# 14-MT7688AN_USB-PCIe.net
KiCad netlist of a schematic drawn in Altium Designer
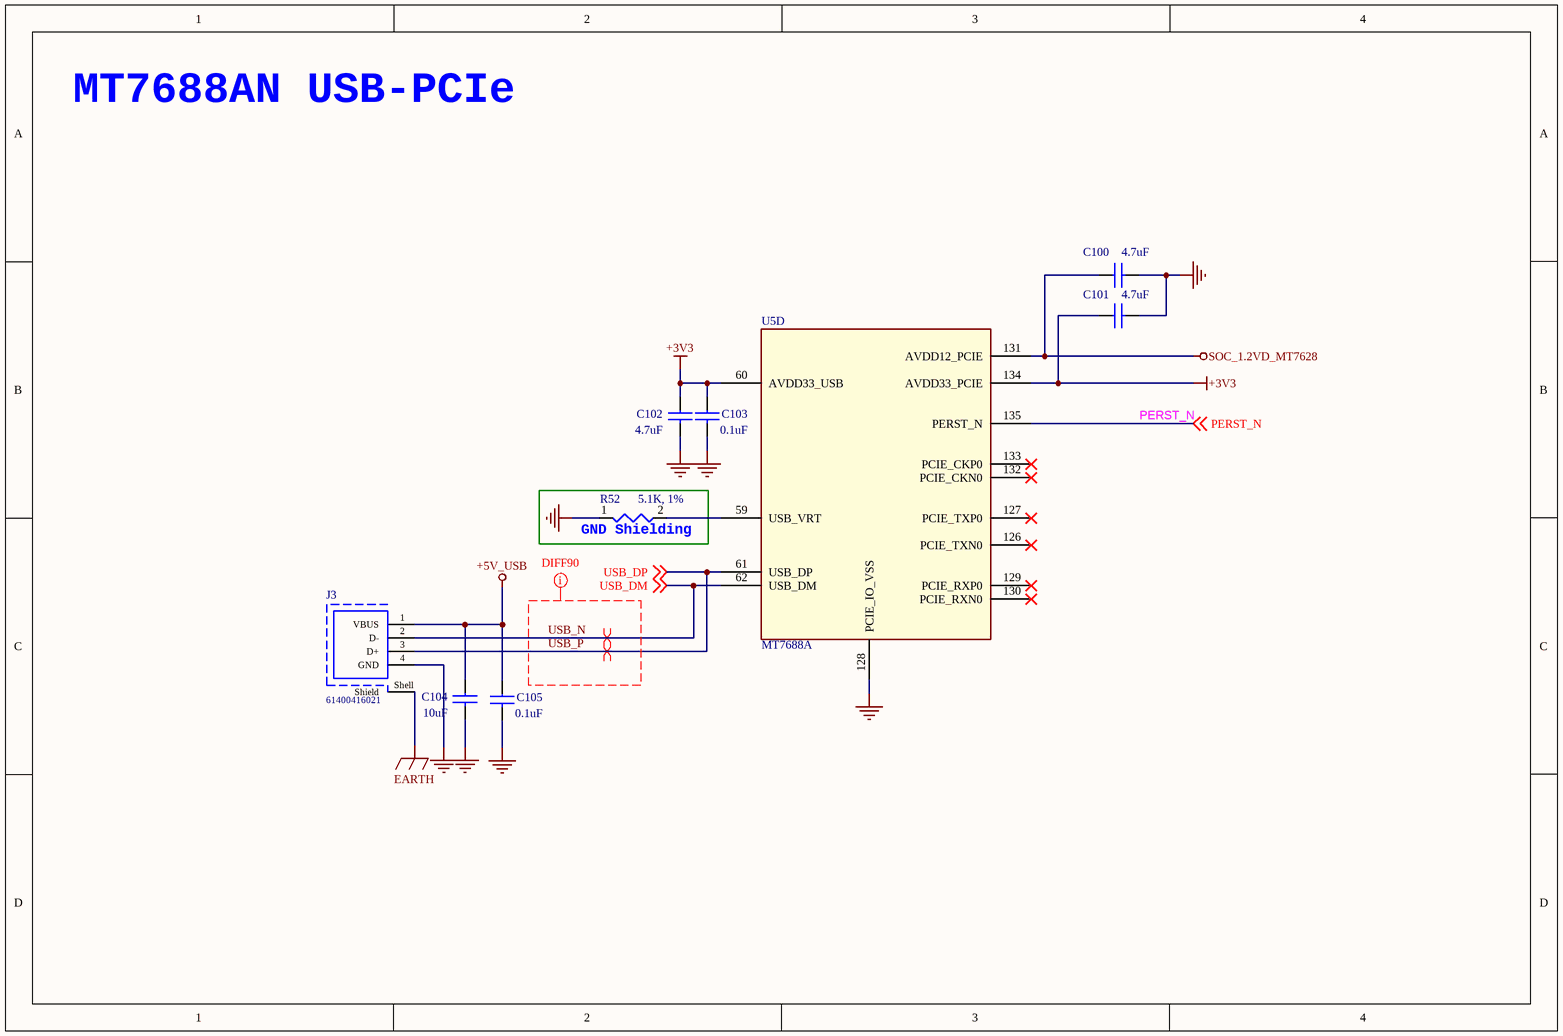
[diagram p0: 14-MT7688AN USB-PCIe.SchDoc]

(export (version "E")
  (design (tool "Eeschema 10.0.6"))
  (components
    (comp (ref "C100")
      (value "4.7uF")
      (footprint "CAPC1005X60X30LL05T10 - duplicate")
      (libsource (lib "MT7688AN") (part "CAP NP"))
    )
    (comp (ref "C101")
      (value "4.7uF")
      (footprint "CAPC1005X60X30LL05T10 - duplicate")
      (libsource (lib "MT7688AN") (part "CAP NP"))
    )
    (comp (ref "C102")
      (value "4.7uF")
      (footprint "CAPC1005X60X30NL05T10")
      (libsource (lib "MT7688AN") (part "CAP NP"))
    )
    (comp (ref "C103")
      (value "0.1uF")
      (footprint "CAPC1005X60X30NL05T10")
      (libsource (lib "MT7688AN") (part "CAP NP"))
    )
    (comp (ref "C104")
      (value "10uF")
      (footprint "CAPC1608X90X35NL10T15")
      (libsource (lib "MT7688AN") (part "CAP NP"))
    )
    (comp (ref "C105")
      (value "0.1uF")
      (footprint "CAPC1005X60X30LL05T10 - duplicate")
      (libsource (lib "MT7688AN") (part "CAP NP"))
    )
    (comp (ref "J3")
      (value "61400416021")
      (footprint "61400416021")
      (description "USB 2.0 Type A Receptacle WR-COM, Horizontal, THT")
      (fields (field (name "MANUFACTURER") "Wurth Elektronik") (field (name "PUBLISHER") "WurthElektronik"))
      (libsource (lib "Altium Content Vault") (part "WE-USB-4-1SHLD"))
    )
    (comp (ref "R52")
      (value "5.1K, 1%")
      (footprint "RESC1005X40X25NL05T10 - duplicate")
      (libsource (lib "MT7688AN") (part "RES/0402_3"))
    )
    (comp (ref "U5")
      (value "MT7688A")
      (footprint "MT7628AN$2F$DRQFN156$2F$SMD$2F$P0.5$2F$12X12")
      (libsource (lib "MT7688AN") (part "MT7620N-n_26"))
    )
  )
  (nets
    (net (code "1") (name "+3V3") (class "Default")
      (node (ref "C101") (pin "1") (pinfunction "1_1") (pintype "passive"))
      (node (ref "C102") (pin "1") (pinfunction "1_1") (pintype "passive"))
      (node (ref "C103") (pin "1") (pinfunction "1_1") (pintype "passive"))
      (node (ref "U5") (pin "134") (pinfunction "AVDD33_PCIE_134") (pintype "power_in"))
      (node (ref "U5") (pin "60") (pinfunction "AVDD33_USB_60") (pintype "passive"))
    )
    (net (code "2") (name "+5V_USB") (class "Default")
      (node (ref "C104") (pin "1") (pinfunction "1_1") (pintype "passive"))
      (node (ref "C105") (pin "1") (pinfunction "1_1") (pintype "passive"))
      (node (ref "J3") (pin "1") (pinfunction "VBUS_1") (pintype "passive"))
    )
    (net (code "3") (name "EARTH") (class "Default")
      (node (ref "J3") (pin "Shell") (pinfunction "Shield_Shell") (pintype "passive"))
    )
    (net (code "4") (name "GND") (class "Default")
      (node (ref "C100") (pin "2") (pinfunction "2_2") (pintype "passive"))
      (node (ref "C101") (pin "2") (pinfunction "2_2") (pintype "passive"))
      (node (ref "C102") (pin "2") (pinfunction "2_2") (pintype "passive"))
      (node (ref "C103") (pin "2") (pinfunction "2_2") (pintype "passive"))
      (node (ref "C104") (pin "2") (pinfunction "2_2") (pintype "passive"))
      (node (ref "C105") (pin "2") (pinfunction "2_2") (pintype "passive"))
      (node (ref "J3") (pin "4") (pinfunction "GND_4") (pintype "passive"))
      (node (ref "R52") (pin "1") (pinfunction "1_1") (pintype "passive"))
      (node (ref "U5") (pin "128") (pinfunction "PCIE_IO_VSS_128") (pintype "passive"))
    )
    (net (code "5") (name "Net-(U5D-USB_VRT)") (class "Default")
      (node (ref "R52") (pin "2") (pinfunction "2_2") (pintype "passive"))
      (node (ref "U5") (pin "59") (pinfunction "USB_VRT_59") (pintype "passive"))
    )
    (net (code "6") (name "PERST_N") (class "Default")
      (node (ref "U5") (pin "135") (pinfunction "PERST_N_135") (pintype "passive"))
    )
    (net (code "7") (name "SOC_1.2VD_MT7628") (class "Default")
      (node (ref "C100") (pin "1") (pinfunction "1_1") (pintype "passive"))
      (node (ref "U5") (pin "131") (pinfunction "AVDD12_PCIE_131") (pintype "power_in"))
    )
    (net (code "8") (name "USB_DM") (class "Default")
      (node (ref "J3") (pin "2") (pinfunction "D-_2") (pintype "passive"))
      (node (ref "U5") (pin "62") (pinfunction "USB_DM_62") (pintype "passive"))
    )
    (net (code "9") (name "USB_DP") (class "Default")
      (node (ref "J3") (pin "3") (pinfunction "D+_3") (pintype "passive"))
      (node (ref "U5") (pin "61") (pinfunction "USB_DP_61") (pintype "passive"))
    )
    (net (code "10") (name "unconnected-(U5D-PCIE_CKN0-Pad132)") (class "Default")
      (node (ref "U5") (pin "132") (pinfunction "PCIE_CKN0_132") (pintype "passive+no_connect"))
    )
    (net (code "11") (name "unconnected-(U5D-PCIE_CKP0-Pad133)") (class "Default")
      (node (ref "U5") (pin "133") (pinfunction "PCIE_CKP0_133") (pintype "passive+no_connect"))
    )
    (net (code "12") (name "unconnected-(U5D-PCIE_RXN0-Pad130)") (class "Default")
      (node (ref "U5") (pin "130") (pinfunction "PCIE_RXN0_130") (pintype "passive+no_connect"))
    )
    (net (code "13") (name "unconnected-(U5D-PCIE_RXP0-Pad129)") (class "Default")
      (node (ref "U5") (pin "129") (pinfunction "PCIE_RXP0_129") (pintype "passive+no_connect"))
    )
    (net (code "14") (name "unconnected-(U5D-PCIE_TXN0-Pad126)") (class "Default")
      (node (ref "U5") (pin "126") (pinfunction "PCIE_TXN0_126") (pintype "passive+no_connect"))
    )
    (net (code "15") (name "unconnected-(U5D-PCIE_TXP0-Pad127)") (class "Default")
      (node (ref "U5") (pin "127") (pinfunction "PCIE_TXP0_127") (pintype "passive+no_connect"))
    )
  )
)
